# Transceiver_for_KNx.net
KiCad netlist of a schematic drawn in Altium Designer
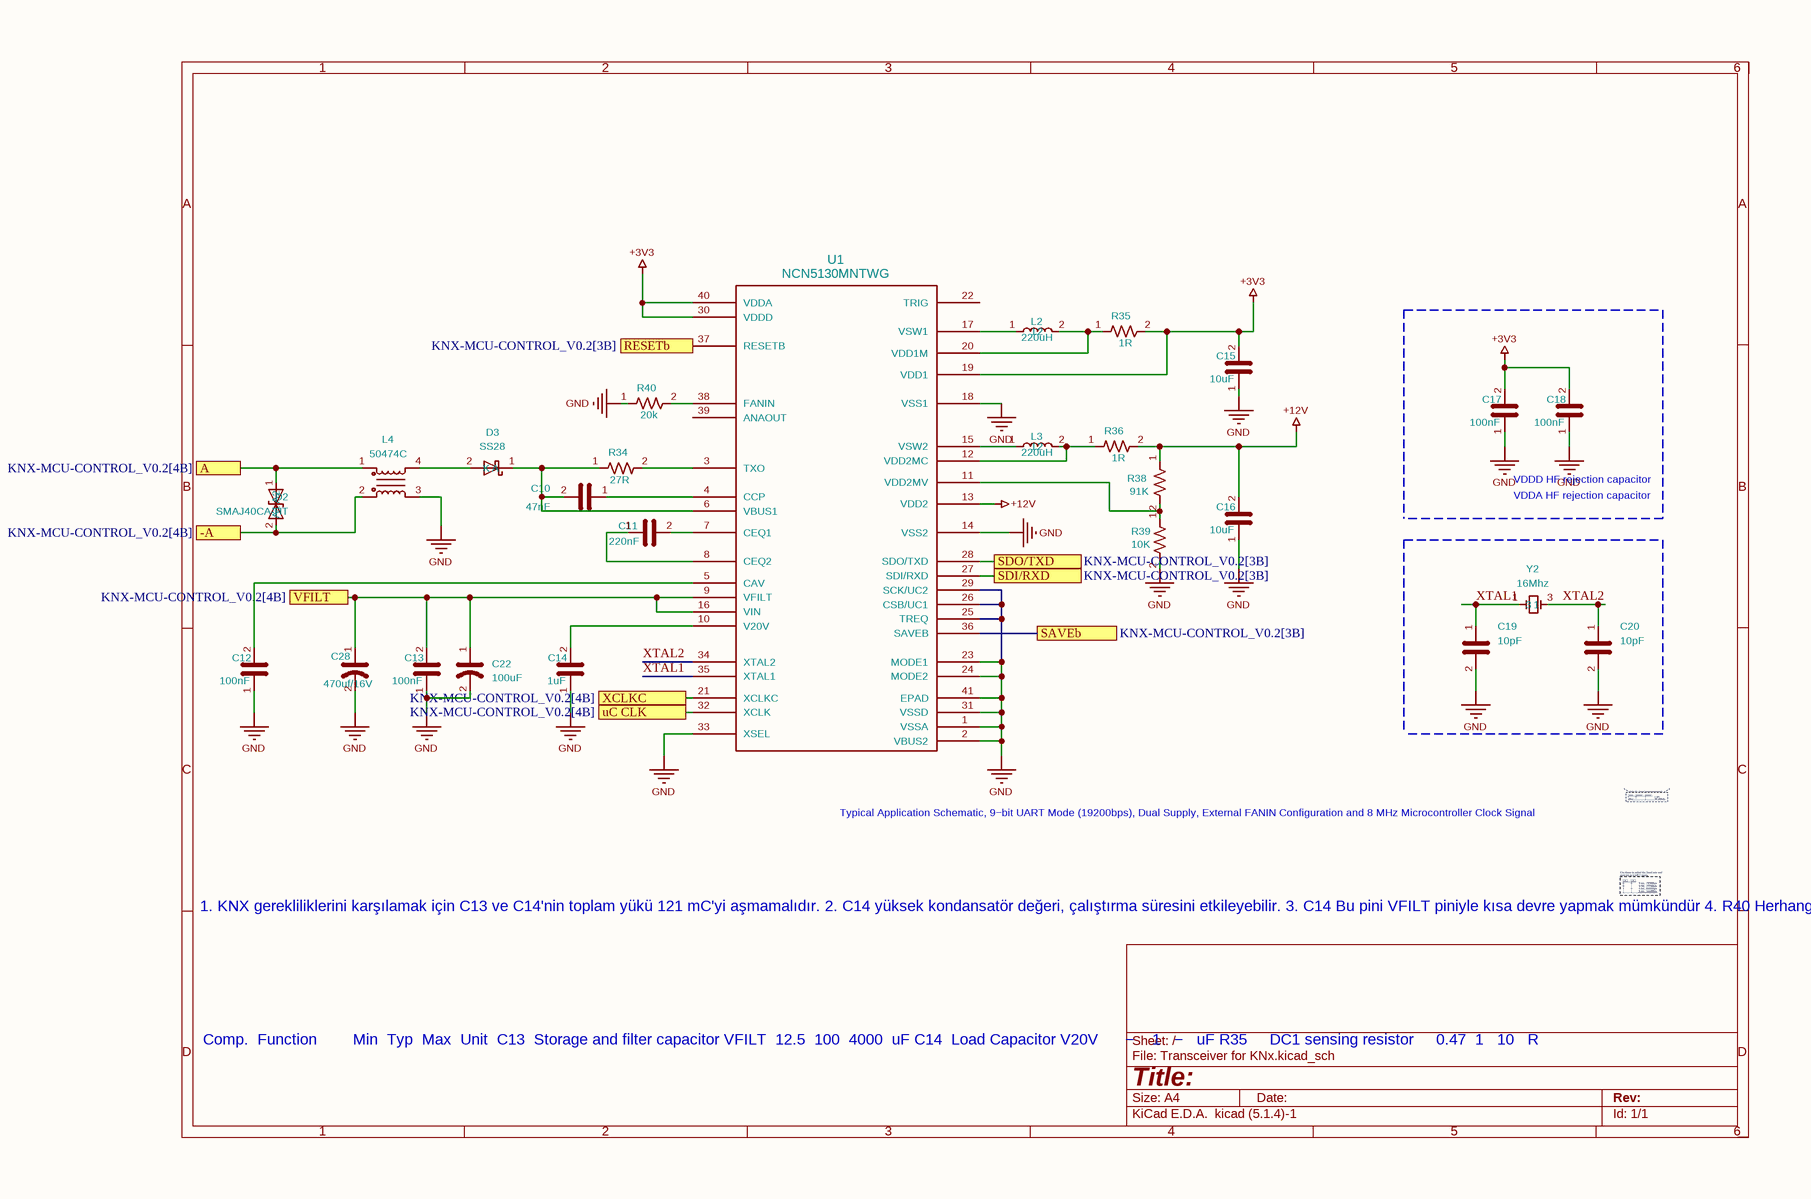
[diagram p0: Transceiver for KNx.SchDoc]

(export (version "E")
  (design (tool "Eeschema 10.0.6"))
  (components
    (comp (ref "C10")
      (value "47nF")
      (footprint "C_0603_1608Metric")
      (fields
        (field (name "MANUFACTURER PART NUMBER") "CL10B473KB8NNNC")
        (field (name "MANUFACTURER") "SAMSUNG")
      )
      (libsource (lib "*") (part "C_3"))
    )
    (comp (ref "C11")
      (value "220nF")
      (footprint "C_0603_1608Metric")
      (fields
        (field (name "MANUFACTURER PART NUMBER") "CL10B224KB8NNNC")
        (field (name "MANUFACTURER") "Samsung Electro-Mechanics")
      )
      (libsource (lib "*") (part "C_3"))
    )
    (comp (ref "C12")
      (value "100nF")
      (footprint "C_0603_1608Metric")
      (fields
        (field (name "MANUFACTURER PART NUMBER") "CL10B104KB8NNNC")
        (field (name "MANUFACTURER") "Samsung Electro-Mechanics")
      )
      (libsource (lib "*") (part "C_1"))
    )
    (comp (ref "C13")
      (value "100nF")
      (footprint "C_0603_1608Metric")
      (fields
        (field (name "MANUFACTURER PART NUMBER") "CL10B104KB8NNNC")
        (field (name "MANUFACTURER") "Samsung Electro-Mechanics")
      )
      (libsource (lib "*") (part "C_1"))
    )
    (comp (ref "C14")
      (value "1uF")
      (footprint "C_0603_1608Metric")
      (fields
        (field (name "MANUFACTURER PART NUMBER") "CL10B105KP8NNNC")
        (field (name "MANUFACTURER") "Samsung Electro-Mechanics")
      )
      (libsource (lib "*") (part "C_3"))
    )
    (comp (ref "C15")
      (value "10uF")
      (footprint "C_0805_2012Metric")
      (fields
        (field (name "MANUFACTURER PART NUMBER") "CL21B106KOQNNNE")
        (field (name "MANUFACTURER") "Samsung Electro-Mechanics")
      )
      (libsource (lib "*") (part "C_3"))
    )
    (comp (ref "C16")
      (value "10uF")
      (footprint "C_0805_2012Metric")
      (fields
        (field (name "MANUFACTURER PART NUMBER") "CL21B106KOQNNNE")
        (field (name "MANUFACTURER") "Samsung Electro-Mechanics")
      )
      (libsource (lib "*") (part "C_3"))
    )
    (comp (ref "C17")
      (value "100nF")
      (footprint "C_0603_1608Metric")
      (fields
        (field (name "MANUFACTURER PART NUMBER") "CL10B104KB8NNNC")
        (field (name "MANUFACTURER") "Samsung Electro-Mechanics")
      )
      (libsource (lib "*") (part "C_1"))
    )
    (comp (ref "C18")
      (value "100nF")
      (footprint "C_0603_1608Metric")
      (fields
        (field (name "MANUFACTURER PART NUMBER") "CL10B104KB8NNNC")
        (field (name "MANUFACTURER") "Samsung Electro-Mechanics")
      )
      (libsource (lib "*") (part "C_1"))
    )
    (comp (ref "C19")
      (value "10pF")
      (footprint "C_0603_1608Metric")
      (fields
        (field (name "MANUFACTURER PART NUMBER") "CL10C100JB8NNNC")
        (field (name "MANUFACTURER") "Samsung Electro-Mechanics")
      )
      (libsource (lib "SparkFun-Capacitor") (part "20pF_0402_50V_5%"))
    )
    (comp (ref "C20")
      (value "10pF")
      (footprint "C_0603_1608Metric")
      (fields
        (field (name "MANUFACTURER PART NUMBER") "CL10C100JB8NNNC")
        (field (name "MANUFACTURER") "Samsung Electro-Mechanics")
      )
      (libsource (lib "SparkFun-Capacitor") (part "20pF_0402_50V_5%"))
    )
    (comp (ref "C22")
      (value "100uF")
      (footprint "CP_Elec_8x10")
      (fields
        (field (name "MANUFACTURER PART NUMBER") "CD035M101F10PKKKV00A")
        (field (name "MANUFACTURER") "SUSCON")
      )
      (libsource (lib "Device") (part "C_US"))
    )
    (comp (ref "C28")
      (value "470uf/16V")
      (footprint "CP_Elec_8x10")
      (description "CAP.EL.470uF 16V 8x10 105C SMD")
      (fields
        (field (name "MANUFACTURER PART NUMBER") "EEEFK1C471P")
        (field (name "MANUFACTURER") "PANASONIC(EUROPE)")
      )
      (libsource (lib "Device") (part "C_US"))
    )
    (comp (ref "D2")
      (value "SMAJ40CA-HT")
      (footprint "D_SMA")
      (fields (field (name "MANUFACTURER") "HOTTECH"))
      (libsource (lib "Device") (part "D_TVS"))
    )
    (comp (ref "D3")
      (value "SS28")
      (footprint "D_SMA")
      (fields (field (name "MANUFACTURER PART NUMBER") "SS18-HT") (field (name "MANUFACTURER") "HOTTECH"))
      (libsource (lib "Diode") (part "SS28"))
    )
    (comp (ref "L2")
      (value "220uH")
      (footprint "L_APV_ANR6028")
      (fields
        (field (name "MANUFACTURER PART NUMBER") "NR6028-221M")
        (field (name "MANUFACTURER") "CORE MASTER")
      )
      (libsource (lib "Device") (part "L"))
    )
    (comp (ref "L3")
      (value "220uH")
      (footprint "L_APV_ANR6028")
      (fields
        (field (name "MANUFACTURER PART NUMBER") "NR6028-221M")
        (field (name "MANUFACTURER") "CORE MASTER")
      )
      (libsource (lib "Device") (part "L"))
    )
    (comp (ref "L4")
      (value "50474C")
      (footprint "L_CommonMode_50474C_7.5x5.9mm")
      (fields (field (name "MANUFACTURER") "muRata"))
      (libsource (lib "Filter") (part "Choke_Wurth_WE-CNSW_744232090"))
    )
    (comp (ref "R34")
      (value "27R")
      (footprint "R_2512_6332Metric")
      (fields
        (field (name "MANUFACTURER PART NUMBER") "HP122WF270JT4E")
        (field (name "MANUFACTURER") "ROYALOHM")
      )
      (libsource (lib "Device") (part "R_US"))
    )
    (comp (ref "R35")
      (value "1R")
      (footprint "R_0805_2012Metric")
      (fields
        (field (name "MANUFACTURER PART NUMBER") "ERJ6RQF1R0V")
        (field (name "MANUFACTURER") "PANASONIC")
      )
      (libsource (lib "Device") (part "R_US"))
    )
    (comp (ref "R36")
      (value "1R")
      (footprint "R_0805_2012Metric")
      (fields
        (field (name "MANUFACTURER PART NUMBER") "ERJ6RQF1R0V")
        (field (name "MANUFACTURER") "PANASONIC")
      )
      (libsource (lib "Device") (part "R_US"))
    )
    (comp (ref "R38")
      (value "91K")
      (footprint "R_0603_1608Metric")
      (fields
        (field (name "MANUFACTURER PART NUMBER") "0603SAF9102T5E")
        (field (name "MANUFACTURER") "ROYALOHM")
      )
      (libsource (lib "Device") (part "R_US"))
    )
    (comp (ref "R39")
      (value "10K")
      (footprint "R_0603_1608Metric")
      (fields
        (field (name "MANUFACTURER PART NUMBER") "PS03W4F1002T5E")
        (field (name "MANUFACTURER") "ROYALOHM")
      )
      (libsource (lib "Device") (part "R_US"))
    )
    (comp (ref "R40")
      (value "20k")
      (footprint "R_0603_1608Metric")
      (fields
        (field (name "MANUFACTURER PART NUMBER") "0603SAF2002T5E")
        (field (name "MANUFACTURER") "ROYALOHM")
      )
      (libsource (lib "Device") (part "R_US"))
    )
    (comp (ref "U1")
      (value "NCN5130MNTWG")
      (footprint "QFN40_485AU-01_ONS")
      (fields (field (name "MANUFACTURER") "onsemi"))
      (libsource (lib "Me_Library") (part "NCN5130MNTWG"))
    )
    (comp (ref "Y2")
      (value "16Mhz")
      (footprint "Crystal_SMD_SeikoEpson_FA238V-4Pin_3.2x2.5mm")
      (fields
        (field (name "MANUFACTURER PART NUMBER") "RH100-16.000-10-1010-EXT")
        (field (name "MANUFACTURER") "RALTRON")
      )
      (libsource (lib "SparkFun-Clock") (part "Crystal"))
    )
  )
  (nets
    (net (code "1") (name "+3V3") (class "Default")
      (node (ref "C15") (pin "2") (pinfunction "2_2") (pintype "passive"))
      (node (ref "C17") (pin "2") (pinfunction "2_2") (pintype "passive"))
      (node (ref "C18") (pin "2") (pinfunction "2_2") (pintype "passive"))
      (node (ref "R35") (pin "2") (pinfunction "2_2") (pintype "passive"))
      (node (ref "U1") (pin "19") (pinfunction "VDD1_19") (pintype "passive"))
      (node (ref "U1") (pin "30") (pinfunction "VDDD_30") (pintype "passive"))
      (node (ref "U1") (pin "40") (pinfunction "VDDA_40") (pintype "passive"))
    )
    (net (code "2") (name "+12V") (class "Default")
      (node (ref "C16") (pin "2") (pinfunction "2_2") (pintype "passive"))
      (node (ref "R36") (pin "2") (pinfunction "2_2") (pintype "passive"))
      (node (ref "R38") (pin "1") (pinfunction "1_1") (pintype "passive"))
      (node (ref "U1") (pin "13") (pinfunction "VDD2_13") (pintype "passive"))
    )
    (net (code "3") (name "/-A") (class "Default")
      (node (ref "D2") (pin "2") (pinfunction "A2_2") (pintype "passive"))
      (node (ref "L4") (pin "2") (pinfunction "2_2") (pintype "passive"))
    )
    (net (code "4") (name "/A") (class "Default")
      (node (ref "D2") (pin "1") (pinfunction "A1_1") (pintype "passive"))
      (node (ref "L4") (pin "1") (pinfunction "1_1") (pintype "passive"))
    )
    (net (code "5") (name "/RESETb") (class "Default")
      (node (ref "U1") (pin "37") (pinfunction "RESETB_37") (pintype "passive"))
    )
    (net (code "6") (name "/SAVEb") (class "Default")
      (node (ref "U1") (pin "36") (pinfunction "SAVEB_36") (pintype "passive"))
    )
    (net (code "7") (name "/SDI{slash}RXD") (class "Default")
      (node (ref "U1") (pin "27") (pinfunction "SDI/RXD_27") (pintype "passive"))
    )
    (net (code "8") (name "/SDO{slash}TXD") (class "Default")
      (node (ref "U1") (pin "28") (pinfunction "SDO/TXD_28") (pintype "passive"))
    )
    (net (code "9") (name "/VFILT") (class "Default")
      (node (ref "C13") (pin "2") (pinfunction "2_2") (pintype "passive"))
      (node (ref "C22") (pin "1") (pinfunction "1_1") (pintype "passive"))
      (node (ref "C28") (pin "1") (pinfunction "1_1") (pintype "passive"))
      (node (ref "U1") (pin "16") (pinfunction "VIN_16") (pintype "passive"))
      (node (ref "U1") (pin "9") (pinfunction "VFILT_9") (pintype "passive"))
    )
    (net (code "10") (name "/XCLKC") (class "Default")
      (node (ref "U1") (pin "21") (pinfunction "XCLKC_21") (pintype "passive"))
    )
    (net (code "11") (name "/XTAL1") (class "Default")
      (node (ref "C19") (pin "1") (pinfunction "1_1") (pintype "passive"))
      (node (ref "U1") (pin "35") (pinfunction "XTAL1_35") (pintype "passive"))
      (node (ref "Y2") (pin "1") (pinfunction "1_1") (pintype "passive"))
    )
    (net (code "12") (name "/XTAL2") (class "Default")
      (node (ref "C20") (pin "1") (pinfunction "1_1") (pintype "passive"))
      (node (ref "U1") (pin "34") (pinfunction "XTAL2_34") (pintype "passive"))
      (node (ref "Y2") (pin "3") (pinfunction "3_3") (pintype "passive"))
    )
    (net (code "13") (name "/uC CLK") (class "Default")
      (node (ref "U1") (pin "32") (pinfunction "XCLK_32") (pintype "passive"))
    )
    (net (code "14") (name "GND") (class "Default")
      (node (ref "C12") (pin "1") (pinfunction "1_1") (pintype "passive"))
      (node (ref "C13") (pin "1") (pinfunction "1_1") (pintype "passive"))
      (node (ref "C14") (pin "1") (pinfunction "1_1") (pintype "passive"))
      (node (ref "C15") (pin "1") (pinfunction "1_1") (pintype "passive"))
      (node (ref "C16") (pin "1") (pinfunction "1_1") (pintype "passive"))
      (node (ref "C17") (pin "1") (pinfunction "1_1") (pintype "passive"))
      (node (ref "C18") (pin "1") (pinfunction "1_1") (pintype "passive"))
      (node (ref "C19") (pin "2") (pinfunction "2_2") (pintype "passive"))
      (node (ref "C20") (pin "2") (pinfunction "2_2") (pintype "passive"))
      (node (ref "C22") (pin "2") (pinfunction "2_2") (pintype "passive"))
      (node (ref "C28") (pin "2") (pinfunction "2_2") (pintype "passive"))
      (node (ref "L4") (pin "3") (pinfunction "3_3") (pintype "passive"))
      (node (ref "R39") (pin "2") (pinfunction "2_2") (pintype "passive"))
      (node (ref "R40") (pin "1") (pinfunction "1_1") (pintype "passive"))
      (node (ref "U1") (pin "1") (pinfunction "VSSA_1") (pintype "passive"))
      (node (ref "U1") (pin "14") (pinfunction "VSS2_14") (pintype "passive"))
      (node (ref "U1") (pin "18") (pinfunction "VSS1_18") (pintype "passive"))
      (node (ref "U1") (pin "2") (pinfunction "VBUS2_2") (pintype "passive"))
      (node (ref "U1") (pin "23") (pinfunction "MODE1_23") (pintype "passive"))
      (node (ref "U1") (pin "24") (pinfunction "MODE2_24") (pintype "passive"))
      (node (ref "U1") (pin "25") (pinfunction "TREQ_25") (pintype "passive"))
      (node (ref "U1") (pin "26") (pinfunction "CSB/UC1_26") (pintype "passive"))
      (node (ref "U1") (pin "29") (pinfunction "SCK/UC2_29") (pintype "passive"))
      (node (ref "U1") (pin "31") (pinfunction "VSSD_31") (pintype "passive"))
      (node (ref "U1") (pin "33") (pinfunction "XSEL_33") (pintype "passive"))
      (node (ref "U1") (pin "41") (pinfunction "EPAD_41") (pintype "passive"))
    )
    (net (code "15") (name "Net-(D3-A)") (class "Default")
      (node (ref "D3") (pin "2") (pinfunction "A_2") (pintype "passive"))
      (node (ref "L4") (pin "4") (pinfunction "4_4") (pintype "passive"))
    )
    (net (code "16") (name "Net-(D3-K)") (class "Default")
      (node (ref "C10") (pin "2") (pinfunction "2_2") (pintype "passive"))
      (node (ref "D3") (pin "1") (pinfunction "K_1") (pintype "passive"))
      (node (ref "R34") (pin "1") (pinfunction "1_1") (pintype "passive"))
      (node (ref "U1") (pin "6") (pinfunction "VBUS1_6") (pintype "passive"))
    )
    (net (code "17") (name "Net-(U1-CAV)") (class "Default")
      (node (ref "C12") (pin "2") (pinfunction "2_2") (pintype "passive"))
      (node (ref "U1") (pin "5") (pinfunction "CAV_5") (pintype "passive"))
    )
    (net (code "18") (name "Net-(U1-CCP)") (class "Default")
      (node (ref "C10") (pin "1") (pinfunction "1_1") (pintype "passive"))
      (node (ref "U1") (pin "4") (pinfunction "CCP_4") (pintype "passive"))
    )
    (net (code "19") (name "Net-(U1-CEQ1)") (class "Default")
      (node (ref "C11") (pin "2") (pinfunction "2_2") (pintype "passive"))
      (node (ref "U1") (pin "7") (pinfunction "CEQ1_7") (pintype "passive"))
    )
    (net (code "20") (name "Net-(U1-CEQ2)") (class "Default")
      (node (ref "C11") (pin "1") (pinfunction "1_1") (pintype "passive"))
      (node (ref "U1") (pin "8") (pinfunction "CEQ2_8") (pintype "passive"))
    )
    (net (code "21") (name "Net-(U1-FANIN)") (class "Default")
      (node (ref "R40") (pin "2") (pinfunction "2_2") (pintype "passive"))
      (node (ref "U1") (pin "38") (pinfunction "FANIN_38") (pintype "passive"))
    )
    (net (code "22") (name "Net-(U1-TXO)") (class "Default")
      (node (ref "R34") (pin "2") (pinfunction "2_2") (pintype "passive"))
      (node (ref "U1") (pin "3") (pinfunction "TXO_3") (pintype "passive"))
    )
    (net (code "23") (name "Net-(U1-V20V)") (class "Default")
      (node (ref "C14") (pin "2") (pinfunction "2_2") (pintype "passive"))
      (node (ref "U1") (pin "10") (pinfunction "V20V_10") (pintype "passive"))
    )
    (net (code "24") (name "Net-(U1-VDD1M)") (class "Default")
      (node (ref "L2") (pin "2") (pinfunction "2_2") (pintype "passive"))
      (node (ref "R35") (pin "1") (pinfunction "1_1") (pintype "passive"))
      (node (ref "U1") (pin "20") (pinfunction "VDD1M_20") (pintype "passive"))
    )
    (net (code "25") (name "Net-(U1-VDD2MC)") (class "Default")
      (node (ref "L3") (pin "2") (pinfunction "2_2") (pintype "passive"))
      (node (ref "R36") (pin "1") (pinfunction "1_1") (pintype "passive"))
      (node (ref "U1") (pin "12") (pinfunction "VDD2MC_12") (pintype "passive"))
    )
    (net (code "26") (name "Net-(U1-VDD2MV)") (class "Default")
      (node (ref "R38") (pin "2") (pinfunction "2_2") (pintype "passive"))
      (node (ref "R39") (pin "1") (pinfunction "1_1") (pintype "passive"))
      (node (ref "U1") (pin "11") (pinfunction "VDD2MV_11") (pintype "passive"))
    )
    (net (code "27") (name "Net-(U1-VSW1)") (class "Default")
      (node (ref "L2") (pin "1") (pinfunction "1_1") (pintype "passive"))
      (node (ref "U1") (pin "17") (pinfunction "VSW1_17") (pintype "passive"))
    )
    (net (code "28") (name "Net-(U1-VSW2)") (class "Default")
      (node (ref "L3") (pin "1") (pinfunction "1_1") (pintype "passive"))
      (node (ref "U1") (pin "15") (pinfunction "VSW2_15") (pintype "passive"))
    )
    (net (code "29") (name "unconnected-(U1-ANAOUT-Pad39)") (class "Default")
      (node (ref "U1") (pin "39") (pinfunction "ANAOUT_39") (pintype "passive"))
    )
    (net (code "30") (name "unconnected-(U1-TRIG-Pad22)") (class "Default")
      (node (ref "U1") (pin "22") (pinfunction "TRIG_22") (pintype "passive"))
    )
  )
)
